# CLOCK.net
KiCad netlist of a schematic drawn in Altium Designer
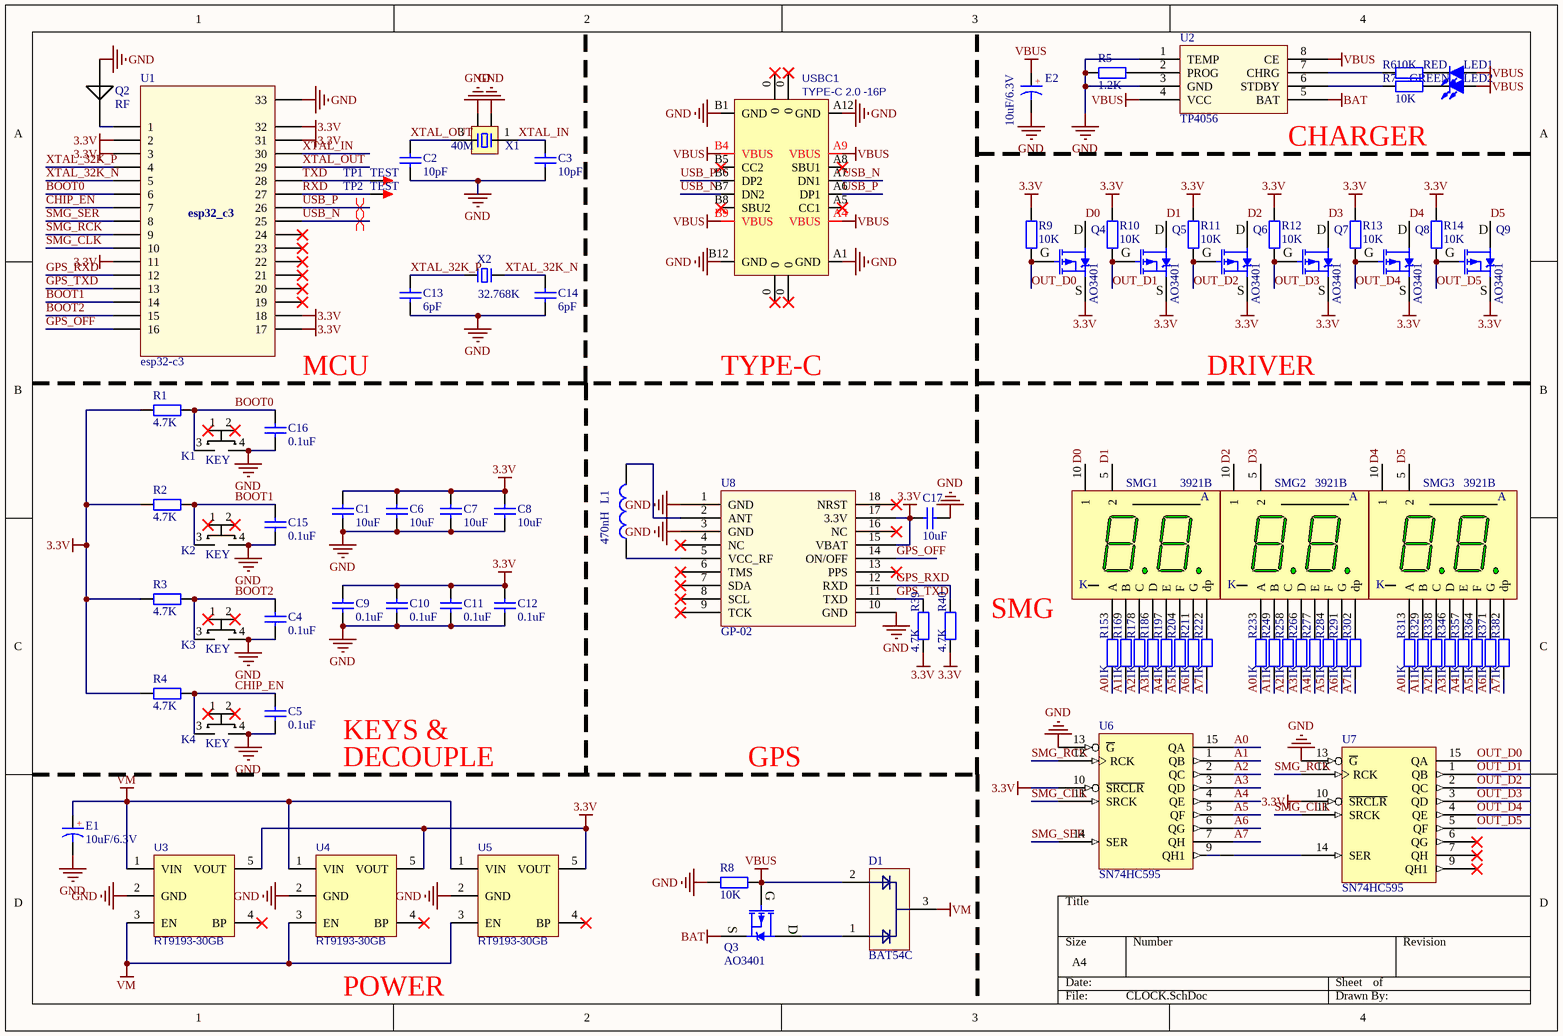
[diagram p0: CLOCK.SchDoc]

(export (version "E")
  (design (tool "Eeschema 10.0.6"))
  (components
    (comp (ref "C1")
      (value "10uF")
      (footprint "C0603_L")
      (description "贴片电容/MLCC电容")
      (libsource (lib "0.1 - 电阻-电容-电感-晶振-晶体-磁珠-电位器-法拉电容-馈通电容") (part "C"))
    )
    (comp (ref "C2")
      (value "10pF")
      (footprint "C0603_L")
      (description "贴片电容/MLCC电容")
      (libsource (lib "0.1 - 电阻-电容-电感-晶振-晶体-磁珠-电位器-法拉电容-馈通电容") (part "C"))
    )
    (comp (ref "C3")
      (value "10pF")
      (footprint "C0603_L")
      (description "贴片电容/MLCC电容")
      (libsource (lib "0.1 - 电阻-电容-电感-晶振-晶体-磁珠-电位器-法拉电容-馈通电容") (part "C"))
    )
    (comp (ref "C4")
      (value "0.1uF")
      (footprint "C0603_L")
      (description "贴片电容/MLCC电容")
      (libsource (lib "0.1 - 电阻-电容-电感-晶振-晶体-磁珠-电位器-法拉电容-馈通电容") (part "C"))
    )
    (comp (ref "C5")
      (value "0.1uF")
      (footprint "C0603_L")
      (description "贴片电容/MLCC电容")
      (libsource (lib "0.1 - 电阻-电容-电感-晶振-晶体-磁珠-电位器-法拉电容-馈通电容") (part "C"))
    )
    (comp (ref "C6")
      (value "10uF")
      (footprint "C0603_L")
      (description "贴片电容/MLCC电容")
      (libsource (lib "0.1 - 电阻-电容-电感-晶振-晶体-磁珠-电位器-法拉电容-馈通电容") (part "C"))
    )
    (comp (ref "C7")
      (value "10uF")
      (footprint "C0603_L")
      (description "贴片电容/MLCC电容")
      (libsource (lib "0.1 - 电阻-电容-电感-晶振-晶体-磁珠-电位器-法拉电容-馈通电容") (part "C"))
    )
    (comp (ref "C8")
      (value "10uF")
      (footprint "C0603_L")
      (description "贴片电容/MLCC电容")
      (libsource (lib "0.1 - 电阻-电容-电感-晶振-晶体-磁珠-电位器-法拉电容-馈通电容") (part "C"))
    )
    (comp (ref "C9")
      (value "0.1uF")
      (footprint "C0603_L")
      (description "贴片电容/MLCC电容")
      (libsource (lib "0.1 - 电阻-电容-电感-晶振-晶体-磁珠-电位器-法拉电容-馈通电容") (part "C"))
    )
    (comp (ref "C10")
      (value "0.1uF")
      (footprint "C0603_L")
      (description "贴片电容/MLCC电容")
      (libsource (lib "0.1 - 电阻-电容-电感-晶振-晶体-磁珠-电位器-法拉电容-馈通电容") (part "C"))
    )
    (comp (ref "C11")
      (value "0.1uF")
      (footprint "C0603_L")
      (description "贴片电容/MLCC电容")
      (libsource (lib "0.1 - 电阻-电容-电感-晶振-晶体-磁珠-电位器-法拉电容-馈通电容") (part "C"))
    )
    (comp (ref "C12")
      (value "0.1uF")
      (footprint "C0603_L")
      (description "贴片电容/MLCC电容")
      (libsource (lib "0.1 - 电阻-电容-电感-晶振-晶体-磁珠-电位器-法拉电容-馈通电容") (part "C"))
    )
    (comp (ref "C13")
      (value "6pF")
      (footprint "C0603_L")
      (description "贴片电容/MLCC电容")
      (libsource (lib "0.1 - 电阻-电容-电感-晶振-晶体-磁珠-电位器-法拉电容-馈通电容") (part "C"))
    )
    (comp (ref "C14")
      (value "6pF")
      (footprint "C0603_L")
      (description "贴片电容/MLCC电容")
      (libsource (lib "0.1 - 电阻-电容-电感-晶振-晶体-磁珠-电位器-法拉电容-馈通电容") (part "C"))
    )
    (comp (ref "C15")
      (value "0.1uF")
      (footprint "C0603_L")
      (description "贴片电容/MLCC电容")
      (libsource (lib "0.1 - 电阻-电容-电感-晶振-晶体-磁珠-电位器-法拉电容-馈通电容") (part "C"))
    )
    (comp (ref "C16")
      (value "0.1uF")
      (footprint "C0603_L")
      (description "贴片电容/MLCC电容")
      (libsource (lib "0.1 - 电阻-电容-电感-晶振-晶体-磁珠-电位器-法拉电容-馈通电容") (part "C"))
    )
    (comp (ref "C17")
      (value "10uF")
      (footprint "C0603_L")
      (description "贴片电容/MLCC电容")
      (libsource (lib "0.1 - 电阻-电容-电感-晶振-晶体-磁珠-电位器-法拉电容-馈通电容") (part "C"))
    )
    (comp (ref "D1")
      (value "BAT54C")
      (footprint "SOT23-3N")
      (description "两路肖特基二极管")
      (libsource (lib "0.2 - 二极管-TVS-ESD-整流桥-放电管") (part "BAT54C"))
    )
    (comp (ref "E1")
      (value "10uF/6.3V")
      (footprint "C_2012")
      (description "贴片钽电容")
      (libsource (lib "0.1 - 电阻-电容-电感-晶振-晶体-磁珠-电位器-法拉电容-馈通电容") (part "CT"))
    )
    (comp (ref "E2")
      (value "10uF/6.3V")
      (footprint "C_2012")
      (description "贴片钽电容")
      (libsource (lib "0.1 - 电阻-电容-电感-晶振-晶体-磁珠-电位器-法拉电容-馈通电容") (part "CT"))
    )
    (comp (ref "K1") (value "KEY") (footprint "KEY") (libsource (lib "CLOCK") (part "KEY")))
    (comp (ref "K2") (value "KEY") (footprint "KEY") (libsource (lib "CLOCK") (part "KEY")))
    (comp (ref "K3") (value "KEY") (footprint "KEY") (libsource (lib "CLOCK") (part "KEY")))
    (comp (ref "K4") (value "KEY") (footprint "KEY") (libsource (lib "CLOCK") (part "KEY")))
    (comp (ref "L1")
      (value "470nH")
      (footprint "L0603")
      (description "贴片小功率电感")
      (libsource (lib "0.1 - 电阻-电容-电感-晶振-晶体-磁珠-电位器-法拉电容-馈通电容") (part "L"))
    )
    (comp (ref "LED1")
      (value "RED")
      (footprint "LED0805_G")
      (description "贴片LED")
      (libsource (lib "0.3 - LED发光二极管-IR二极管_接收管-光耦") (part "LED-SMD"))
    )
    (comp (ref "LED2")
      (value "GREEN")
      (footprint "LED0805_G")
      (description "贴片LED")
      (libsource (lib "0.3 - LED发光二极管-IR二极管_接收管-光耦") (part "LED-SMD"))
    )
    (comp (ref "Q2") (value "RF") (footprint "RF") (libsource (lib "motor") (part "RF")))
    (comp (ref "Q3")
      (value "AO3401")
      (footprint "SOT23-3N")
      (description "P沟道 30V/4.2A")
      (libsource (lib "0.4 - 三极管-场效应管-可控硅") (part "AO3401"))
    )
    (comp (ref "Q4")
      (value "AO3401")
      (footprint "SOT23-3N")
      (description "P沟道 30V/4.2A")
      (libsource (lib "0.4 - 三极管-场效应管-可控硅") (part "AO3401"))
    )
    (comp (ref "Q5")
      (value "AO3401")
      (footprint "SOT23-3N")
      (description "P沟道 30V/4.2A")
      (libsource (lib "0.4 - 三极管-场效应管-可控硅") (part "AO3401"))
    )
    (comp (ref "Q6")
      (value "AO3401")
      (footprint "SOT23-3N")
      (description "P沟道 30V/4.2A")
      (libsource (lib "0.4 - 三极管-场效应管-可控硅") (part "AO3401"))
    )
    (comp (ref "Q7")
      (value "AO3401")
      (footprint "SOT23-3N")
      (description "P沟道 30V/4.2A")
      (libsource (lib "0.4 - 三极管-场效应管-可控硅") (part "AO3401"))
    )
    (comp (ref "Q8")
      (value "AO3401")
      (footprint "SOT23-3N")
      (description "P沟道 30V/4.2A")
      (libsource (lib "0.4 - 三极管-场效应管-可控硅") (part "AO3401"))
    )
    (comp (ref "Q9")
      (value "AO3401")
      (footprint "SOT23-3N")
      (description "P沟道 30V/4.2A")
      (libsource (lib "0.4 - 三极管-场效应管-可控硅") (part "AO3401"))
    )
    (comp (ref "R1")
      (value "4.7K")
      (footprint "R0603_L")
      (description "贴片电阻")
      (libsource (lib "0.1 - 电阻-电容-电感-晶振-晶体-磁珠-电位器-法拉电容-馈通电容") (part "R"))
    )
    (comp (ref "R2")
      (value "4.7K")
      (footprint "R0603_L")
      (description "贴片电阻")
      (libsource (lib "0.1 - 电阻-电容-电感-晶振-晶体-磁珠-电位器-法拉电容-馈通电容") (part "R"))
    )
    (comp (ref "R3")
      (value "4.7K")
      (footprint "R0603_L")
      (description "贴片电阻")
      (libsource (lib "0.1 - 电阻-电容-电感-晶振-晶体-磁珠-电位器-法拉电容-馈通电容") (part "R"))
    )
    (comp (ref "R4")
      (value "4.7K")
      (footprint "R0603_L")
      (description "贴片电阻")
      (libsource (lib "0.1 - 电阻-电容-电感-晶振-晶体-磁珠-电位器-法拉电容-馈通电容") (part "R"))
    )
    (comp (ref "R5")
      (value "1.2K")
      (footprint "R0603_L")
      (description "贴片电阻")
      (libsource (lib "0.1 - 电阻-电容-电感-晶振-晶体-磁珠-电位器-法拉电容-馈通电容") (part "R"))
    )
    (comp (ref "R6")
      (value "10K")
      (footprint "R0603_L")
      (description "贴片电阻")
      (libsource (lib "0.1 - 电阻-电容-电感-晶振-晶体-磁珠-电位器-法拉电容-馈通电容") (part "R"))
    )
    (comp (ref "R7")
      (value "10K")
      (footprint "R0603_L")
      (description "贴片电阻")
      (libsource (lib "0.1 - 电阻-电容-电感-晶振-晶体-磁珠-电位器-法拉电容-馈通电容") (part "R"))
    )
    (comp (ref "R8")
      (value "10K")
      (footprint "R0603_L")
      (description "贴片电阻")
      (libsource (lib "0.1 - 电阻-电容-电感-晶振-晶体-磁珠-电位器-法拉电容-馈通电容") (part "R"))
    )
    (comp (ref "R9")
      (value "10K")
      (footprint "R0603_L")
      (description "贴片电阻")
      (libsource (lib "0.1 - 电阻-电容-电感-晶振-晶体-磁珠-电位器-法拉电容-馈通电容") (part "R"))
    )
    (comp (ref "R10")
      (value "10K")
      (footprint "R0603_L")
      (description "贴片电阻")
      (libsource (lib "0.1 - 电阻-电容-电感-晶振-晶体-磁珠-电位器-法拉电容-馈通电容") (part "R"))
    )
    (comp (ref "R11")
      (value "10K")
      (footprint "R0603_L")
      (description "贴片电阻")
      (libsource (lib "0.1 - 电阻-电容-电感-晶振-晶体-磁珠-电位器-法拉电容-馈通电容") (part "R"))
    )
    (comp (ref "R12")
      (value "10K")
      (footprint "R0603_L")
      (description "贴片电阻")
      (libsource (lib "0.1 - 电阻-电容-电感-晶振-晶体-磁珠-电位器-法拉电容-馈通电容") (part "R"))
    )
    (comp (ref "R13")
      (value "10K")
      (footprint "R0603_L")
      (description "贴片电阻")
      (libsource (lib "0.1 - 电阻-电容-电感-晶振-晶体-磁珠-电位器-法拉电容-馈通电容") (part "R"))
    )
    (comp (ref "R14")
      (value "10K")
      (footprint "R0603_L")
      (description "贴片电阻")
      (libsource (lib "0.1 - 电阻-电容-电感-晶振-晶体-磁珠-电位器-法拉电容-馈通电容") (part "R"))
    )
    (comp (ref "R15")
      (value "1K")
      (footprint "R0603_L")
      (description "贴片电阻")
      (libsource (lib "0.1 - 电阻-电容-电感-晶振-晶体-磁珠-电位器-法拉电容-馈通电容") (part "R"))
    )
    (comp (ref "R16")
      (value "1K")
      (footprint "R0603_L")
      (description "贴片电阻")
      (libsource (lib "0.1 - 电阻-电容-电感-晶振-晶体-磁珠-电位器-法拉电容-馈通电容") (part "R"))
    )
    (comp (ref "R17")
      (value "1K")
      (footprint "R0603_L")
      (description "贴片电阻")
      (libsource (lib "0.1 - 电阻-电容-电感-晶振-晶体-磁珠-电位器-法拉电容-馈通电容") (part "R"))
    )
    (comp (ref "R18")
      (value "1K")
      (footprint "R0603_L")
      (description "贴片电阻")
      (libsource (lib "0.1 - 电阻-电容-电感-晶振-晶体-磁珠-电位器-法拉电容-馈通电容") (part "R"))
    )
    (comp (ref "R19")
      (value "1K")
      (footprint "R0603_L")
      (description "贴片电阻")
      (libsource (lib "0.1 - 电阻-电容-电感-晶振-晶体-磁珠-电位器-法拉电容-馈通电容") (part "R"))
    )
    (comp (ref "R20")
      (value "1K")
      (footprint "R0603_L")
      (description "贴片电阻")
      (libsource (lib "0.1 - 电阻-电容-电感-晶振-晶体-磁珠-电位器-法拉电容-馈通电容") (part "R"))
    )
    (comp (ref "R21")
      (value "1K")
      (footprint "R0603_L")
      (description "贴片电阻")
      (libsource (lib "0.1 - 电阻-电容-电感-晶振-晶体-磁珠-电位器-法拉电容-馈通电容") (part "R"))
    )
    (comp (ref "R22")
      (value "1K")
      (footprint "R0603_L")
      (description "贴片电阻")
      (libsource (lib "0.1 - 电阻-电容-电感-晶振-晶体-磁珠-电位器-法拉电容-馈通电容") (part "R"))
    )
    (comp (ref "R23")
      (value "1K")
      (footprint "R0603_L")
      (description "贴片电阻")
      (libsource (lib "0.1 - 电阻-电容-电感-晶振-晶体-磁珠-电位器-法拉电容-馈通电容") (part "R"))
    )
    (comp (ref "R24")
      (value "1K")
      (footprint "R0603_L")
      (description "贴片电阻")
      (libsource (lib "0.1 - 电阻-电容-电感-晶振-晶体-磁珠-电位器-法拉电容-馈通电容") (part "R"))
    )
    (comp (ref "R25")
      (value "1K")
      (footprint "R0603_L")
      (description "贴片电阻")
      (libsource (lib "0.1 - 电阻-电容-电感-晶振-晶体-磁珠-电位器-法拉电容-馈通电容") (part "R"))
    )
    (comp (ref "R26")
      (value "1K")
      (footprint "R0603_L")
      (description "贴片电阻")
      (libsource (lib "0.1 - 电阻-电容-电感-晶振-晶体-磁珠-电位器-法拉电容-馈通电容") (part "R"))
    )
    (comp (ref "R27")
      (value "1K")
      (footprint "R0603_L")
      (description "贴片电阻")
      (libsource (lib "0.1 - 电阻-电容-电感-晶振-晶体-磁珠-电位器-法拉电容-馈通电容") (part "R"))
    )
    (comp (ref "R28")
      (value "1K")
      (footprint "R0603_L")
      (description "贴片电阻")
      (libsource (lib "0.1 - 电阻-电容-电感-晶振-晶体-磁珠-电位器-法拉电容-馈通电容") (part "R"))
    )
    (comp (ref "R29")
      (value "1K")
      (footprint "R0603_L")
      (description "贴片电阻")
      (libsource (lib "0.1 - 电阻-电容-电感-晶振-晶体-磁珠-电位器-法拉电容-馈通电容") (part "R"))
    )
    (comp (ref "R30")
      (value "1K")
      (footprint "R0603_L")
      (description "贴片电阻")
      (libsource (lib "0.1 - 电阻-电容-电感-晶振-晶体-磁珠-电位器-法拉电容-馈通电容") (part "R"))
    )
    (comp (ref "R31")
      (value "1K")
      (footprint "R0603_L")
      (description "贴片电阻")
      (libsource (lib "0.1 - 电阻-电容-电感-晶振-晶体-磁珠-电位器-法拉电容-馈通电容") (part "R"))
    )
    (comp (ref "R32")
      (value "1K")
      (footprint "R0603_L")
      (description "贴片电阻")
      (libsource (lib "0.1 - 电阻-电容-电感-晶振-晶体-磁珠-电位器-法拉电容-馈通电容") (part "R"))
    )
    (comp (ref "R33")
      (value "1K")
      (footprint "R0603_L")
      (description "贴片电阻")
      (libsource (lib "0.1 - 电阻-电容-电感-晶振-晶体-磁珠-电位器-法拉电容-馈通电容") (part "R"))
    )
    (comp (ref "R34")
      (value "1K")
      (footprint "R0603_L")
      (description "贴片电阻")
      (libsource (lib "0.1 - 电阻-电容-电感-晶振-晶体-磁珠-电位器-法拉电容-馈通电容") (part "R"))
    )
    (comp (ref "R35")
      (value "1K")
      (footprint "R0603_L")
      (description "贴片电阻")
      (libsource (lib "0.1 - 电阻-电容-电感-晶振-晶体-磁珠-电位器-法拉电容-馈通电容") (part "R"))
    )
    (comp (ref "R36")
      (value "1K")
      (footprint "R0603_L")
      (description "贴片电阻")
      (libsource (lib "0.1 - 电阻-电容-电感-晶振-晶体-磁珠-电位器-法拉电容-馈通电容") (part "R"))
    )
    (comp (ref "R37")
      (value "1K")
      (footprint "R0603_L")
      (description "贴片电阻")
      (libsource (lib "0.1 - 电阻-电容-电感-晶振-晶体-磁珠-电位器-法拉电容-馈通电容") (part "R"))
    )
    (comp (ref "R38")
      (value "1K")
      (footprint "R0603_L")
      (description "贴片电阻")
      (libsource (lib "0.1 - 电阻-电容-电感-晶振-晶体-磁珠-电位器-法拉电容-馈通电容") (part "R"))
    )
    (comp (ref "R39")
      (value "4.7K")
      (footprint "R0603_L")
      (description "贴片电阻")
      (libsource (lib "0.1 - 电阻-电容-电感-晶振-晶体-磁珠-电位器-法拉电容-馈通电容") (part "R"))
    )
    (comp (ref "R40")
      (value "4.7K")
      (footprint "R0603_L")
      (description "贴片电阻")
      (libsource (lib "0.1 - 电阻-电容-电感-晶振-晶体-磁珠-电位器-法拉电容-馈通电容") (part "R"))
    )
    (comp (ref "SMG1")
      (value "3921B")
      (footprint "GS3922CPG-G")
      (description "0.39寸2位共阳数码管")
      (libsource (lib "1.3 - 数码管-TFT-OLED屏") (part "3921B"))
    )
    (comp (ref "SMG2")
      (value "3921B")
      (footprint "GS3922CPG-G")
      (description "0.39寸2位共阳数码管")
      (libsource (lib "1.3 - 数码管-TFT-OLED屏") (part "3921B"))
    )
    (comp (ref "SMG3")
      (value "3921B")
      (footprint "GS3922CPG-G")
      (description "0.39寸2位共阳数码管")
      (libsource (lib "1.3 - 数码管-TFT-OLED屏") (part "3921B"))
    )
    (comp (ref "TP1")
      (value "TEST")
      (footprint "TEST 1.6")
      (description "测试点")
      (libsource (lib "0.5 - 按键_开关_蜂鸣器_保险丝_电池_测试点_Mark点_铜柱") (part "TEST"))
    )
    (comp (ref "TP2")
      (value "TEST")
      (footprint "TEST 1.6")
      (description "测试点")
      (libsource (lib "0.5 - 按键_开关_蜂鸣器_保险丝_电池_测试点_Mark点_铜柱") (part "TEST"))
    )
    (comp (ref "U1") (value "esp32-c3") (footprint "QFN32 5x5_M") (libsource (lib "motor") (part "esp32-c3")))
    (comp (ref "U2") (value "TP4056") (footprint "SOP-8") (libsource (lib "CLOCK") (part "TP4056")))
    (comp (ref "U3")
      (value "RT9193-30GB")
      (footprint "SOT-23-5")
      (description "LDO 3.0V/0.3A")
      (libsource (lib "0.7 - 电源类芯片") (part "RT9193-30GB"))
    )
    (comp (ref "U4")
      (value "RT9193-30GB")
      (footprint "SOT-23-5")
      (description "LDO 3.0V/0.3A")
      (libsource (lib "0.7 - 电源类芯片") (part "RT9193-30GB"))
    )
    (comp (ref "U5")
      (value "RT9193-30GB")
      (footprint "SOT-23-5")
      (description "LDO 3.0V/0.3A")
      (libsource (lib "0.7 - 电源类芯片") (part "RT9193-30GB"))
    )
    (comp (ref "U6")
      (value "SN74HC595")
      (footprint "SO16")
      (description "8-BIT SFT REG WIRTH OUTPUT LCH")
      (libsource (lib "1.1 - 74系列TTL逻辑芯片") (part "SN74HC595"))
    )
    (comp (ref "U7")
      (value "SN74HC595")
      (footprint "SO16")
      (description "8-BIT SFT REG WIRTH OUTPUT LCH")
      (libsource (lib "1.1 - 74系列TTL逻辑芯片") (part "SN74HC595"))
    )
    (comp (ref "U8") (value "GP-02") (footprint "GP-02") (libsource (lib "CLOCK") (part "GP-02")))
    (comp (ref "USBC1")
      (value "TYPE-C 2.0 -16P")
      (footprint "USB-C-SMD_16P")
      (description "USB2.0_Type-C_16Pin母座")
      (libsource (lib "0.6 - 电源_RJ45以太网_音频_SD-TF_SIM_ USB Type-C_HDMI插座") (part "USB2.0_Type-C_16Pin"))
    )
    (comp (ref "X1")
      (value "40M")
      (footprint "XTAL-3225-4P")
      (description "4脚无源晶振(谐振器）")
      (libsource (lib "0.1 - 电阻-电容-电感-晶振-晶体-磁珠-电位器-法拉电容-馈通电容") (part "XTAL-4P"))
    )
    (comp (ref "X2")
      (value "32.768K")
      (footprint "XTAL-3x8-WS")
      (description "2脚无源晶振(谐振器）")
      (libsource (lib "0.1 - 电阻-电容-电感-晶振-晶体-磁珠-电位器-法拉电容-馈通电容") (part "XTAL-2P"))
    )
  )
  (nets
    (net (code "1") (name "/A0") (class "Default")
      (node (ref "R15") (pin "1") (pinfunction "1_1") (pintype "passive"))
      (node (ref "R23") (pin "1") (pinfunction "1_1") (pintype "passive"))
      (node (ref "R31") (pin "1") (pinfunction "1_1") (pintype "passive"))
      (node (ref "U6") (pin "15") (pinfunction "QA_15") (pintype "tri_state"))
    )
    (net (code "2") (name "/A1") (class "Default")
      (node (ref "R16") (pin "1") (pinfunction "1_1") (pintype "passive"))
      (node (ref "R24") (pin "1") (pinfunction "1_1") (pintype "passive"))
      (node (ref "R32") (pin "1") (pinfunction "1_1") (pintype "passive"))
      (node (ref "U6") (pin "1") (pinfunction "QB_1") (pintype "output"))
    )
    (net (code "3") (name "/A2") (class "Default")
      (node (ref "R17") (pin "1") (pinfunction "1_1") (pintype "passive"))
      (node (ref "R25") (pin "1") (pinfunction "1_1") (pintype "passive"))
      (node (ref "R33") (pin "1") (pinfunction "1_1") (pintype "passive"))
      (node (ref "U6") (pin "2") (pinfunction "QC_2") (pintype "output"))
    )
    (net (code "4") (name "/A3") (class "Default")
      (node (ref "R18") (pin "1") (pinfunction "1_1") (pintype "passive"))
      (node (ref "R26") (pin "1") (pinfunction "1_1") (pintype "passive"))
      (node (ref "R34") (pin "1") (pinfunction "1_1") (pintype "passive"))
      (node (ref "U6") (pin "3") (pinfunction "QD_3") (pintype "output"))
    )
    (net (code "5") (name "/A4") (class "Default")
      (node (ref "R19") (pin "1") (pinfunction "1_1") (pintype "passive"))
      (node (ref "R27") (pin "1") (pinfunction "1_1") (pintype "passive"))
      (node (ref "R35") (pin "1") (pinfunction "1_1") (pintype "passive"))
      (node (ref "U6") (pin "4") (pinfunction "QE_4") (pintype "output"))
    )
    (net (code "6") (name "/A5") (class "Default")
      (node (ref "R20") (pin "1") (pinfunction "1_1") (pintype "passive"))
      (node (ref "R28") (pin "1") (pinfunction "1_1") (pintype "passive"))
      (node (ref "R36") (pin "1") (pinfunction "1_1") (pintype "passive"))
      (node (ref "U6") (pin "5") (pinfunction "QF_5") (pintype "output"))
    )
    (net (code "7") (name "/A6") (class "Default")
      (node (ref "R21") (pin "1") (pinfunction "1_1") (pintype "passive"))
      (node (ref "R29") (pin "1") (pinfunction "1_1") (pintype "passive"))
      (node (ref "R37") (pin "1") (pinfunction "1_1") (pintype "passive"))
      (node (ref "U6") (pin "6") (pinfunction "QG_6") (pintype "output"))
    )
    (net (code "8") (name "/A7") (class "Default")
      (node (ref "R22") (pin "1") (pinfunction "1_1") (pintype "passive"))
      (node (ref "R30") (pin "1") (pinfunction "1_1") (pintype "passive"))
      (node (ref "R38") (pin "1") (pinfunction "1_1") (pintype "passive"))
      (node (ref "U6") (pin "7") (pinfunction "QH_7") (pintype "tri_state"))
    )
    (net (code "9") (name "/BOOT0") (class "Default")
      (node (ref "C16") (pin "2") (pinfunction "2_2") (pintype "passive"))
      (node (ref "K1") (pin "3") (pintype "passive"))
      (node (ref "R1") (pin "2") (pinfunction "2_2") (pintype "passive"))
      (node (ref "U1") (pin "6") (pinfunction "6_6") (pintype "passive"))
    )
    (net (code "10") (name "/BOOT1") (class "Default")
      (node (ref "C15") (pin "2") (pinfunction "2_2") (pintype "passive"))
      (node (ref "K2") (pin "3") (pintype "passive"))
      (node (ref "R2") (pin "2") (pinfunction "2_2") (pintype "passive"))
      (node (ref "U1") (pin "14") (pinfunction "14_14") (pintype "passive"))
    )
    (net (code "11") (name "/BOOT2") (class "Default")
      (node (ref "C4") (pin "2") (pinfunction "2_2") (pintype "passive"))
      (node (ref "K3") (pin "3") (pintype "passive"))
      (node (ref "R3") (pin "2") (pinfunction "2_2") (pintype "passive"))
      (node (ref "U1") (pin "15") (pinfunction "15_15") (pintype "passive"))
    )
    (net (code "12") (name "/CHIP_EN") (class "Default")
      (node (ref "C5") (pin "2") (pinfunction "2_2") (pintype "passive"))
      (node (ref "K4") (pin "3") (pintype "passive"))
      (node (ref "R4") (pin "2") (pinfunction "2_2") (pintype "passive"))
      (node (ref "U1") (pin "7") (pinfunction "7_7") (pintype "passive"))
    )
    (net (code "13") (name "/D0") (class "Default")
      (node (ref "Q4") (pin "3") (pinfunction "D_3") (pintype "passive"))
      (node (ref "SMG1") (pin "10") (pinfunction "1_10") (pintype "passive"))
    )
    (net (code "14") (name "/D1") (class "Default")
      (node (ref "Q5") (pin "3") (pinfunction "D_3") (pintype "passive"))
      (node (ref "SMG1") (pin "5") (pinfunction "2_5") (pintype "passive"))
    )
    (net (code "15") (name "/D2") (class "Default")
      (node (ref "Q6") (pin "3") (pinfunction "D_3") (pintype "passive"))
      (node (ref "SMG2") (pin "10") (pinfunction "1_10") (pintype "passive"))
    )
    (net (code "16") (name "/D3") (class "Default")
      (node (ref "Q7") (pin "3") (pinfunction "D_3") (pintype "passive"))
      (node (ref "SMG2") (pin "5") (pinfunction "2_5") (pintype "passive"))
    )
    (net (code "17") (name "/D4") (class "Default")
      (node (ref "Q8") (pin "3") (pinfunction "D_3") (pintype "passive"))
      (node (ref "SMG3") (pin "10") (pinfunction "1_10") (pintype "passive"))
    )
    (net (code "18") (name "/D5") (class "Default")
      (node (ref "Q9") (pin "3") (pinfunction "D_3") (pintype "passive"))
      (node (ref "SMG3") (pin "5") (pinfunction "2_5") (pintype "passive"))
    )
    (net (code "19") (name "/GPS_OFF") (class "Default")
      (node (ref "U1") (pin "16") (pinfunction "16_16") (pintype "passive"))
      (node (ref "U8") (pin "14") (pinfunction "ON/OFF_14") (pintype "passive"))
    )
    (net (code "20") (name "/GPS_RXD") (class "Default")
      (node (ref "R40") (pin "2") (pinfunction "2_2") (pintype "passive"))
      (node (ref "U1") (pin "12") (pinfunction "12_12") (pintype "passive"))
      (node (ref "U8") (pin "12") (pinfunction "RXD_12") (pintype "passive"))
    )
    (net (code "21") (name "/GPS_TXD") (class "Default")
      (node (ref "R39") (pin "2") (pinfunction "2_2") (pintype "passive"))
      (node (ref "U1") (pin "13") (pinfunction "13_13") (pintype "passive"))
      (node (ref "U8") (pin "11") (pinfunction "TXD_11") (pintype "passive"))
    )
    (net (code "22") (name "/OUT_D0") (class "Default")
      (node (ref "Q4") (pin "1") (pinfunction "G_1") (pintype "passive"))
      (node (ref "R9") (pin "1") (pinfunction "1_1") (pintype "passive"))
      (node (ref "U7") (pin "15") (pinfunction "QA_15") (pintype "tri_state"))
    )
    (net (code "23") (name "/OUT_D1") (class "Default")
      (node (ref "Q5") (pin "1") (pinfunction "G_1") (pintype "passive"))
      (node (ref "R10") (pin "1") (pinfunction "1_1") (pintype "passive"))
      (node (ref "U7") (pin "1") (pinfunction "QB_1") (pintype "output"))
    )
    (net (code "24") (name "/OUT_D2") (class "Default")
      (node (ref "Q6") (pin "1") (pinfunction "G_1") (pintype "passive"))
      (node (ref "R11") (pin "1") (pinfunction "1_1") (pintype "passive"))
      (node (ref "U7") (pin "2") (pinfunction "QC_2") (pintype "output"))
    )
    (net (code "25") (name "/OUT_D3") (class "Default")
      (node (ref "Q7") (pin "1") (pinfunction "G_1") (pintype "passive"))
      (node (ref "R12") (pin "1") (pinfunction "1_1") (pintype "passive"))
      (node (ref "U7") (pin "3") (pinfunction "QD_3") (pintype "output"))
    )
    (net (code "26") (name "/OUT_D4") (class "Default")
      (node (ref "Q8") (pin "1") (pinfunction "G_1") (pintype "passive"))
      (node (ref "R13") (pin "1") (pinfunction "1_1") (pintype "passive"))
      (node (ref "U7") (pin "4") (pinfunction "QE_4") (pintype "output"))
    )
    (net (code "27") (name "/OUT_D5") (class "Default")
      (node (ref "Q9") (pin "1") (pinfunction "G_1") (pintype "passive"))
      (node (ref "R14") (pin "1") (pinfunction "1_1") (pintype "passive"))
      (node (ref "U7") (pin "5") (pinfunction "QF_5") (pintype "output"))
    )
    (net (code "28") (name "/RXD") (class "Default")
      (node (ref "TP2") (pin "1") (pinfunction "1_1") (pintype "passive"))
      (node (ref "U1") (pin "27") (pinfunction "27_27") (pintype "passive"))
    )
    (net (code "29") (name "/SMG_CLK") (class "Default")
      (node (ref "U1") (pin "10") (pinfunction "10_10") (pintype "passive"))
      (node (ref "U6") (pin "11") (pinfunction "SRCK_11") (pintype "input"))
      (node (ref "U7") (pin "11") (pinfunction "SRCK_11") (pintype "input"))
    )
    (net (code "30") (name "/SMG_RCK") (class "Default")
      (node (ref "U1") (pin "9") (pinfunction "9_9") (pintype "passive"))
      (node (ref "U6") (pin "12") (pinfunction "RCK_12") (pintype "input"))
      (node (ref "U7") (pin "12") (pinfunction "RCK_12") (pintype "input"))
    )
    (net (code "31") (name "/SMG_SER") (class "Default")
      (node (ref "U1") (pin "8") (pinfunction "8_8") (pintype "passive"))
      (node (ref "U6") (pin "14") (pinfunction "SER_14") (pintype "input"))
    )
    (net (code "32") (name "/TXD") (class "Default")
      (node (ref "TP1") (pin "1") (pinfunction "1_1") (pintype "passive"))
      (node (ref "U1") (pin "28") (pinfunction "28_28") (pintype "passive"))
    )
    (net (code "33") (name "/USB_N") (class "Default")
      (node (ref "U1") (pin "25") (pinfunction "25_25") (pintype "passive"))
      (node (ref "USBC1") (pin "A7") (pinfunction "DN1_A7") (pintype "passive"))
      (node (ref "USBC1") (pin "B7") (pinfunction "DN2_B7") (pintype "passive"))
    )
    (net (code "34") (name "/USB_P") (class "Default")
      (node (ref "U1") (pin "26") (pinfunction "26_26") (pintype "passive"))
      (node (ref "USBC1") (pin "A6") (pinfunction "DP1_A6") (pintype "passive"))
      (node (ref "USBC1") (pin "B6") (pinfunction "DP2_B6") (pintype "passive"))
    )
    (net (code "35") (name "/XTAL_32K_N") (class "Default")
      (node (ref "C14") (pin "2") (pinfunction "2_2") (pintype "passive"))
      (node (ref "U1") (pin "5") (pinfunction "5_5") (pintype "passive"))
      (node (ref "X2") (pin "2") (pinfunction "2_2") (pintype "passive"))
    )
    (net (code "36") (name "/XTAL_32K_P") (class "Default")
      (node (ref "C13") (pin "2") (pinfunction "2_2") (pintype "passive"))
      (node (ref "U1") (pin "4") (pinfunction "4_4") (pintype "passive"))
      (node (ref "X2") (pin "1") (pinfunction "1_1") (pintype "passive"))
    )
    (net (code "37") (name "/XTAL_IN") (class "Default")
      (node (ref "C3") (pin "2") (pinfunction "2_2") (pintype "passive"))
      (node (ref "U1") (pin "30") (pinfunction "30_30") (pintype "passive"))
      (node (ref "X1") (pin "1") (pinfunction "1_1") (pintype "passive"))
    )
    (net (code "38") (name "/XTAL_OUT") (class "Default")
      (node (ref "C2") (pin "2") (pinfunction "2_2") (pintype "passive"))
      (node (ref "U1") (pin "29") (pinfunction "29_29") (pintype "passive"))
      (node (ref "X1") (pin "3") (pinfunction "3_3") (pintype "passive"))
    )
    (net (code "39") (name "3.3V") (class "Default")
      (node (ref "C1") (pin "2") (pinfunction "2_2") (pintype "passive"))
      (node (ref "C10") (pin "2") (pinfunction "2_2") (pintype "passive"))
      (node (ref "C11") (pin "2") (pinfunction "2_2") (pintype "passive"))
      (node (ref "C12") (pin "2") (pinfunction "2_2") (pintype "passive"))
      (node (ref "C17") (pin "2") (pinfunction "2_2") (pintype "passive"))
      (node (ref "C6") (pin "2") (pinfunction "2_2") (pintype "passive"))
      (node (ref "C7") (pin "2") (pinfunction "2_2") (pintype "passive"))
      (node (ref "C8") (pin "2") (pinfunction "2_2") (pintype "passive"))
      (node (ref "C9") (pin "2") (pinfunction "2_2") (pintype "passive"))
      (node (ref "Q4") (pin "2") (pinfunction "S_2") (pintype "passive"))
      (node (ref "Q5") (pin "2") (pinfunction "S_2") (pintype "passive"))
      (node (ref "Q6") (pin "2") (pinfunction "S_2") (pintype "passive"))
      (node (ref "Q7") (pin "2") (pinfunction "S_2") (pintype "passive"))
      (node (ref "Q8") (pin "2") (pinfunction "S_2") (pintype "passive"))
      (node (ref "Q9") (pin "2") (pinfunction "S_2") (pintype "passive"))
      (node (ref "R1") (pin "1") (pinfunction "1_1") (pintype "passive"))
      (node (ref "R10") (pin "2") (pinfunction "2_2") (pintype "passive"))
      (node (ref "R11") (pin "2") (pinfunction "2_2") (pintype "passive"))
      (node (ref "R12") (pin "2") (pinfunction "2_2") (pintype "passive"))
      (node (ref "R13") (pin "2") (pinfunction "2_2") (pintype "passive"))
      (node (ref "R14") (pin "2") (pinfunction "2_2") (pintype "passive"))
      (node (ref "R2") (pin "1") (pinfunction "1_1") (pintype "passive"))
      (node (ref "R3") (pin "1") (pinfunction "1_1") (pintype "passive"))
      (node (ref "R39") (pin "1") (pinfunction "1_1") (pintype "passive"))
      (node (ref "R4") (pin "1") (pinfunction "1_1") (pintype "passive"))
      (node (ref "R40") (pin "1") (pinfunction "1_1") (pintype "passive"))
      (node (ref "R9") (pin "2") (pinfunction "2_2") (pintype "passive"))
      (node (ref "U1") (pin "11") (pinfunction "11_11") (pintype "passive"))
      (node (ref "U1") (pin "17") (pinfunction "17_17") (pintype "passive"))
      (node (ref "U1") (pin "18") (pinfunction "18_18") (pintype "passive"))
      (node (ref "U1") (pin "2") (pinfunction "2_2") (pintype "passive"))
      (node (ref "U1") (pin "3") (pinfunction "3_3") (pintype "passive"))
      (node (ref "U1") (pin "31") (pinfunction "31_31") (pintype "passive"))
      (node (ref "U1") (pin "32") (pinfunction "32_32") (pintype "passive"))
      (node (ref "U3") (pin "5") (pinfunction "VOUT_5") (pintype "passive"))
      (node (ref "U4") (pin "5") (pinfunction "VOUT_5") (pintype "passive"))
      (node (ref "U5") (pin "5") (pinfunction "VOUT_5") (pintype "passive"))
      (node (ref "U6") (pin "10") (pinfunction "~{SRCLR}_10") (pintype "input"))
      (node (ref "U7") (pin "10") (pinfunction "~{SRCLR}_10") (pintype "input"))
      (node (ref "U8") (pin "15") (pinfunction "VBAT_15") (pintype "passive"))
      (node (ref "U8") (pin "17") (pinfunction "3.3V_17") (pintype "passive"))
    )
    (net (code "40") (name "BAT") (class "Default")
      (node (ref "Q3") (pin "2") (pinfunction "S_2") (pintype "passive"))
      (node (ref "U2") (pin "5") (pinfunction "BAT_5") (pintype "passive"))
    )
    (net (code "41") (name "GND") (class "Default")
      (node (ref "C1") (pin "1") (pinfunction "1_1") (pintype "passive"))
      (node (ref "C10") (pin "1") (pinfunction "1_1") (pintype "passive"))
      (node (ref "C11") (pin "1") (pinfunction "1_1") (pintype "passive"))
      (node (ref "C12") (pin "1") (pinfunction "1_1") (pintype "passive"))
      (node (ref "C13") (pin "1") (pinfunction "1_1") (pintype "passive"))
      (node (ref "C14") (pin "1") (pinfunction "1_1") (pintype "passive"))
      (node (ref "C15") (pin "1") (pinfunction "1_1") (pintype "passive"))
      (node (ref "C16") (pin "1") (pinfunction "1_1") (pintype "passive"))
      (node (ref "C17") (pin "1") (pinfunction "1_1") (pintype "passive"))
      (node (ref "C2") (pin "1") (pinfunction "1_1") (pintype "passive"))
      (node (ref "C3") (pin "1") (pinfunction "1_1") (pintype "passive"))
      (node (ref "C4") (pin "1") (pinfunction "1_1") (pintype "passive"))
      (node (ref "C5") (pin "1") (pinfunction "1_1") (pintype "passive"))
      (node (ref "C6") (pin "1") (pinfunction "1_1") (pintype "passive"))
      (node (ref "C7") (pin "1") (pinfunction "1_1") (pintype "passive"))
      (node (ref "C8") (pin "1") (pinfunction "1_1") (pintype "passive"))
      (node (ref "C9") (pin "1") (pinfunction "1_1") (pintype "passive"))
      (node (ref "E1") (pin "2") (pinfunction "K_2") (pintype "passive"))
      (node (ref "E2") (pin "2") (pinfunction "K_2") (pintype "passive"))
      (node (ref "K1") (pin "4") (pintype "passive"))
      (node (ref "K2") (pin "4") (pintype "passive"))
      (node (ref "K3") (pin "4") (pintype "passive"))
      (node (ref "K4") (pin "4") (pintype "passive"))
      (node (ref "Q2") (pin "1") (pinfunction "1_1") (pintype "passive"))
      (node (ref "R5") (pin "1") (pinfunction "1_1") (pintype "passive"))
      (node (ref "R8") (pin "1") (pinfunction "1_1") (pintype "passive"))
      (node (ref "U1") (pin "33") (pinfunction "33_33") (pintype "passive"))
      (node (ref "U2") (pin "1") (pinfunction "TEMP_1") (pintype "passive"))
      (node (ref "U2") (pin "3") (pinfunction "GND_3") (pintype "passive"))
      (node (ref "U3") (pin "2") (pinfunction "GND_2") (pintype "passive"))
      (node (ref "U4") (pin "2") (pinfunction "GND_2") (pintype "passive"))
      (node (ref "U5") (pin "2") (pinfunction "GND_2") (pintype "passive"))
      (node (ref "U6") (pin "13") (pinfunction "~{G}_13") (pintype "input"))
      (node (ref "U6") (pin "8") (pinfunction "GND_8") (pintype "power_in"))
      (node (ref "U7") (pin "13") (pinfunction "~{G}_13") (pintype "input"))
      (node (ref "U7") (pin "8") (pinfunction "GND_8") (pintype "power_in"))
      (node (ref "U8") (pin "1") (pinfunction "GND_1") (pintype "passive"))
      (node (ref "U8") (pin "10") (pinfunction "GND_10") (pintype "passive"))
      (node (ref "U8") (pin "3") (pinfunction "GND_3") (pintype "passive"))
      (node (ref "USBC1") (pin "A1") (pinfunction "GND_A1") (pintype "passive"))
      (node (ref "USBC1") (pin "A12") (pinfunction "GND_A12") (pintype "passive"))
      (node (ref "USBC1") (pin "B1") (pinfunction "GND_B1") (pintype "passive"))
      (node (ref "USBC1") (pin "B12") (pinfunction "GND_B12") (pintype "passive"))
      (node (ref "X1") (pin "2") (pinfunction "2_2") (pintype "passive"))
      (node (ref "X1") (pin "4") (pinfunction "4_4") (pintype "passive"))
    )
    (net (code "42") (name "Net-(LED1-K)") (class "Default")
      (node (ref "LED1") (pin "2") (pinfunction "K_2") (pintype "passive"))
      (node (ref "R6") (pin "1") (pinfunction "1_1") (pintype "passive"))
    )
    (net (code "43") (name "Net-(LED2-K)") (class "Default")
      (node (ref "LED2") (pin "2") (pinfunction "K_2") (pintype "passive"))
      (node (ref "R7") (pin "1") (pinfunction "1_1") (pintype "passive"))
    )
    (net (code "44") (name "Net-(Q2-Pad2)") (class "Default")
      (node (ref "Q2") (pin "2") (pinfunction "2_2") (pintype "passive"))
      (node (ref "U1") (pin "1") (pinfunction "1_1") (pintype "passive"))
    )
    (net (code "45") (name "Net-(Q3-D)") (class "Default")
      (node (ref "D1") (pin "1") (pinfunction "1_1") (pintype "passive"))
      (node (ref "Q3") (pin "3") (pinfunction "D_3") (pintype "passive"))
    )
    (net (code "46") (name "Net-(SMG1-A)") (class "Default")
      (node (ref "R15") (pin "2") (pinfunction "2_2") (pintype "passive"))
      (node (ref "SMG1") (pin "3") (pinfunction "A_3") (pintype "passive"))
    )
    (net (code "47") (name "Net-(SMG1-B)") (class "Default")
      (node (ref "R16") (pin "2") (pinfunction "2_2") (pintype "passive"))
      (node (ref "SMG1") (pin "9") (pinfunction "B_9") (pintype "passive"))
    )
    (net (code "48") (name "Net-(SMG1-C)") (class "Default")
      (node (ref "R17") (pin "2") (pinfunction "2_2") (pintype "passive"))
      (node (ref "SMG1") (pin "8") (pinfunction "C_8") (pintype "passive"))
    )
    (net (code "49") (name "Net-(SMG1-D)") (class "Default")
      (node (ref "R18") (pin "2") (pinfunction "2_2") (pintype "passive"))
      (node (ref "SMG1") (pin "6") (pinfunction "D_6") (pintype "passive"))
    )
    (net (code "50") (name "Net-(SMG1-E)") (class "Default")
      (node (ref "R19") (pin "2") (pinfunction "2_2") (pintype "passive"))
      (node (ref "SMG1") (pin "7") (pinfunction "E_7") (pintype "passive"))
    )
    (net (code "51") (name "Net-(SMG1-F)") (class "Default")
      (node (ref "R20") (pin "2") (pinfunction "2_2") (pintype "passive"))
      (node (ref "SMG1") (pin "4") (pinfunction "F_4") (pintype "passive"))
    )
    (net (code "52") (name "Net-(SMG1-G)") (class "Default")
      (node (ref "R21") (pin "2") (pinfunction "2_2") (pintype "passive"))
      (node (ref "SMG1") (pin "1") (pinfunction "G_1") (pintype "passive"))
    )
    (net (code "53") (name "Net-(SMG1-dp)") (class "Default")
      (node (ref "R22") (pin "2") (pinfunction "2_2") (pintype "passive"))
      (node (ref "SMG1") (pin "2") (pinfunction "dp_2") (pintype "passive"))
    )
    (net (code "54") (name "Net-(SMG2-A)") (class "Default")
      (node (ref "R23") (pin "2") (pinfunction "2_2") (pintype "passive"))
      (node (ref "SMG2") (pin "3") (pinfunction "A_3") (pintype "passive"))
    )
    (net (code "55") (name "Net-(SMG2-B)") (class "Default")
      (node (ref "R24") (pin "2") (pinfunction "2_2") (pintype "passive"))
      (node (ref "SMG2") (pin "9") (pinfunction "B_9") (pintype "passive"))
    )
    (net (code "56") (name "Net-(SMG2-C)") (class "Default")
      (node (ref "R25") (pin "2") (pinfunction "2_2") (pintype "passive"))
      (node (ref "SMG2") (pin "8") (pinfunction "C_8") (pintype "passive"))
    )
    (net (code "57") (name "Net-(SMG2-D)") (class "Default")
      (node (ref "R26") (pin "2") (pinfunction "2_2") (pintype "passive"))
      (node (ref "SMG2") (pin "6") (pinfunction "D_6") (pintype "passive"))
    )
    (net (code "58") (name "Net-(SMG2-E)") (class "Default")
      (node (ref "R27") (pin "2") (pinfunction "2_2") (pintype "passive"))
      (node (ref "SMG2") (pin "7") (pinfunction "E_7") (pintype "passive"))
    )
    (net (code "59") (name "Net-(SMG2-F)") (class "Default")
      (node (ref "R28") (pin "2") (pinfunction "2_2") (pintype "passive"))
      (node (ref "SMG2") (pin "4") (pinfunction "F_4") (pintype "passive"))
    )
    (net (code "60") (name "Net-(SMG2-G)") (class "Default")
      (node (ref "R29") (pin "2") (pinfunction "2_2") (pintype "passive"))
      (node (ref "SMG2") (pin "1") (pinfunction "G_1") (pintype "passive"))
    )
    (net (code "61") (name "Net-(SMG2-dp)") (class "Default")
      (node (ref "R30") (pin "2") (pinfunction "2_2") (pintype "passive"))
      (node (ref "SMG2") (pin "2") (pinfunction "dp_2") (pintype "passive"))
    )
    (net (code "62") (name "Net-(SMG3-A)") (class "Default")
      (node (ref "R31") (pin "2") (pinfunction "2_2") (pintype "passive"))
      (node (ref "SMG3") (pin "3") (pinfunction "A_3") (pintype "passive"))
    )
    (net (code "63") (name "Net-(SMG3-B)") (class "Default")
      (node (ref "R32") (pin "2") (pinfunction "2_2") (pintype "passive"))
      (node (ref "SMG3") (pin "9") (pinfunction "B_9") (pintype "passive"))
    )
    (net (code "64") (name "Net-(SMG3-C)") (class "Default")
      (node (ref "R33") (pin "2") (pinfunction "2_2") (pintype "passive"))
      (node (ref "SMG3") (pin "8") (pinfunction "C_8") (pintype "passive"))
    )
    (net (code "65") (name "Net-(SMG3-D)") (class "Default")
      (node (ref "R34") (pin "2") (pinfunction "2_2") (pintype "passive"))
      (node (ref "SMG3") (pin "6") (pinfunction "D_6") (pintype "passive"))
    )
    (net (code "66") (name "Net-(SMG3-E)") (class "Default")
      (node (ref "R35") (pin "2") (pinfunction "2_2") (pintype "passive"))
      (node (ref "SMG3") (pin "7") (pinfunction "E_7") (pintype "passive"))
    )
    (net (code "67") (name "Net-(SMG3-F)") (class "Default")
      (node (ref "R36") (pin "2") (pinfunction "2_2") (pintype "passive"))
      (node (ref "SMG3") (pin "4") (pinfunction "F_4") (pintype "passive"))
    )
    (net (code "68") (name "Net-(SMG3-G)") (class "Default")
      (node (ref "R37") (pin "2") (pinfunction "2_2") (pintype "passive"))
      (node (ref "SMG3") (pin "1") (pinfunction "G_1") (pintype "passive"))
    )
    (net (code "69") (name "Net-(SMG3-dp)") (class "Default")
      (node (ref "R38") (pin "2") (pinfunction "2_2") (pintype "passive"))
      (node (ref "SMG3") (pin "2") (pinfunction "dp_2") (pintype "passive"))
    )
    (net (code "70") (name "Net-(U2-CHRG)") (class "Default")
      (node (ref "R6") (pin "2") (pinfunction "2_2") (pintype "passive"))
      (node (ref "U2") (pin "7") (pinfunction "CHRG_7") (pintype "passive"))
    )
    (net (code "71") (name "Net-(U2-PROG)") (class "Default")
      (node (ref "R5") (pin "2") (pinfunction "2_2") (pintype "passive"))
      (node (ref "U2") (pin "2") (pinfunction "PROG_2") (pintype "passive"))
    )
    (net (code "72") (name "Net-(U2-STDBY)") (class "Default")
      (node (ref "R7") (pin "2") (pinfunction "2_2") (pintype "passive"))
      (node (ref "U2") (pin "6") (pinfunction "STDBY_6") (pintype "passive"))
    )
    (net (code "73") (name "Net-(U6-QH1)") (class "Default")
      (node (ref "U6") (pin "9") (pinfunction "QH1_9") (pintype "output"))
      (node (ref "U7") (pin "14") (pinfunction "SER_14") (pintype "input"))
    )
    (net (code "74") (name "Net-(U8-ANT)") (class "Default")
      (node (ref "L1") (pin "2") (pinfunction "2_2") (pintype "passive"))
      (node (ref "U8") (pin "2") (pinfunction "ANT_2") (pintype "passive"))
    )
    (net (code "75") (name "Net-(U8-VCC_RF)") (class "Default")
      (node (ref "L1") (pin "1") (pinfunction "1_1") (pintype "passive"))
      (node (ref "U8") (pin "5") (pinfunction "VCC_RF_5") (pintype "passive"))
    )
    (net (code "76") (name "VBUS") (class "Default")
      (node (ref "D1") (pin "2") (pinfunction "2_2") (pintype "passive"))
      (node (ref "E2") (pin "1") (pinfunction "A_1") (pintype "passive"))
      (node (ref "LED1") (pin "1") (pinfunction "A_1") (pintype "passive"))
      (node (ref "LED2") (pin "1") (pinfunction "A_1") (pintype "passive"))
      (node (ref "Q3") (pin "1") (pinfunction "G_1") (pintype "passive"))
      (node (ref "R8") (pin "2") (pinfunction "2_2") (pintype "passive"))
      (node (ref "U2") (pin "4") (pinfunction "VCC_4") (pintype "passive"))
      (node (ref "U2") (pin "8") (pinfunction "CE_8") (pintype "passive"))
      (node (ref "USBC1") (pin "A4") (pinfunction "VBUS_A4") (pintype "passive"))
      (node (ref "USBC1") (pin "A9") (pinfunction "VBUS_A9") (pintype "passive"))
      (node (ref "USBC1") (pin "B4") (pinfunction "VBUS_B4") (pintype "passive"))
      (node (ref "USBC1") (pin "B9") (pinfunction "VBUS_B9") (pintype "passive"))
    )
    (net (code "77") (name "VCC") (class "Default")
      (node (ref "U6") (pin "16") (pinfunction "VCC_16") (pintype "power_in"))
      (node (ref "U7") (pin "16") (pinfunction "VCC_16") (pintype "power_in"))
    )
    (net (code "78") (name "VM") (class "Default")
      (node (ref "D1") (pin "3") (pinfunction "3_3") (pintype "passive"))
      (node (ref "E1") (pin "1") (pinfunction "A_1") (pintype "passive"))
      (node (ref "U3") (pin "1") (pinfunction "VIN_1") (pintype "passive"))
      (node (ref "U3") (pin "3") (pinfunction "EN_3") (pintype "passive"))
      (node (ref "U4") (pin "1") (pinfunction "VIN_1") (pintype "passive"))
      (node (ref "U4") (pin "3") (pinfunction "EN_3") (pintype "passive"))
      (node (ref "U5") (pin "1") (pinfunction "VIN_1") (pintype "passive"))
      (node (ref "U5") (pin "3") (pinfunction "EN_3") (pintype "passive"))
    )
    (net (code "79") (name "unconnected-(K1-Pad1)") (class "Default")
      (node (ref "K1") (pin "1") (pintype "passive+no_connect"))
    )
    (net (code "80") (name "unconnected-(K1-Pad2)") (class "Default")
      (node (ref "K1") (pin "2") (pintype "passive+no_connect"))
    )
    (net (code "81") (name "unconnected-(K2-Pad1)") (class "Default")
      (node (ref "K2") (pin "1") (pintype "passive+no_connect"))
    )
    (net (code "82") (name "unconnected-(K2-Pad2)") (class "Default")
      (node (ref "K2") (pin "2") (pintype "passive+no_connect"))
    )
    (net (code "83") (name "unconnected-(K3-Pad1)") (class "Default")
      (node (ref "K3") (pin "1") (pintype "passive+no_connect"))
    )
    (net (code "84") (name "unconnected-(K3-Pad2)") (class "Default")
      (node (ref "K3") (pin "2") (pintype "passive+no_connect"))
    )
    (net (code "85") (name "unconnected-(K4-Pad1)") (class "Default")
      (node (ref "K4") (pin "1") (pintype "passive+no_connect"))
    )
    (net (code "86") (name "unconnected-(K4-Pad2)") (class "Default")
      (node (ref "K4") (pin "2") (pintype "passive+no_connect"))
    )
    (net (code "87") (name "unconnected-(U1-Pad19)") (class "Default")
      (node (ref "U1") (pin "19") (pinfunction "19_19") (pintype "passive+no_connect"))
    )
    (net (code "88") (name "unconnected-(U1-Pad20)") (class "Default")
      (node (ref "U1") (pin "20") (pinfunction "20_20") (pintype "passive+no_connect"))
    )
    (net (code "89") (name "unconnected-(U1-Pad21)") (class "Default")
      (node (ref "U1") (pin "21") (pinfunction "21_21") (pintype "passive+no_connect"))
    )
    (net (code "90") (name "unconnected-(U1-Pad22)") (class "Default")
      (node (ref "U1") (pin "22") (pinfunction "22_22") (pintype "passive+no_connect"))
    )
    (net (code "91") (name "unconnected-(U1-Pad23)") (class "Default")
      (node (ref "U1") (pin "23") (pinfunction "23_23") (pintype "passive+no_connect"))
    )
    (net (code "92") (name "unconnected-(U1-Pad24)") (class "Default")
      (node (ref "U1") (pin "24") (pinfunction "24_24") (pintype "passive+no_connect"))
    )
    (net (code "93") (name "unconnected-(U3-BP-Pad4)") (class "Default")
      (node (ref "U3") (pin "4") (pinfunction "BP_4") (pintype "passive+no_connect"))
    )
    (net (code "94") (name "unconnected-(U4-BP-Pad4)") (class "Default")
      (node (ref "U4") (pin "4") (pinfunction "BP_4") (pintype "passive+no_connect"))
    )
    (net (code "95") (name "unconnected-(U5-BP-Pad4)") (class "Default")
      (node (ref "U5") (pin "4") (pinfunction "BP_4") (pintype "passive+no_connect"))
    )
    (net (code "96") (name "unconnected-(U7-QG-Pad6)") (class "Default")
      (node (ref "U7") (pin "6") (pinfunction "QG_6") (pintype "output+no_connect"))
    )
    (net (code "97") (name "unconnected-(U7-QH-Pad7)") (class "Default")
      (node (ref "U7") (pin "7") (pinfunction "QH_7") (pintype "tri_state+no_connect"))
    )
    (net (code "98") (name "unconnected-(U7-QH1-Pad9)") (class "Default")
      (node (ref "U7") (pin "9") (pinfunction "QH1_9") (pintype "output+no_connect"))
    )
    (net (code "99") (name "unconnected-(U8-NC-Pad4)") (class "Default")
      (node (ref "U8") (pin "4") (pinfunction "NC_4") (pintype "passive+no_connect"))
    )
    (net (code "100") (name "unconnected-(U8-NC-Pad16)") (class "Default")
      (node (ref "U8") (pin "16") (pinfunction "NC_16") (pintype "passive+no_connect"))
    )
    (net (code "101") (name "unconnected-(U8-NRST-Pad18)") (class "Default")
      (node (ref "U8") (pin "18") (pinfunction "NRST_18") (pintype "passive+no_connect"))
    )
    (net (code "102") (name "unconnected-(U8-PPS-Pad13)") (class "Default")
      (node (ref "U8") (pin "13") (pinfunction "PPS_13") (pintype "passive+no_connect"))
    )
    (net (code "103") (name "unconnected-(U8-SCL-Pad8)") (class "Default")
      (node (ref "U8") (pin "8") (pinfunction "SCL_8") (pintype "passive+no_connect"))
    )
    (net (code "104") (name "unconnected-(U8-SDA-Pad7)") (class "Default")
      (node (ref "U8") (pin "7") (pinfunction "SDA_7") (pintype "passive+no_connect"))
    )
    (net (code "105") (name "unconnected-(U8-TCK-Pad9)") (class "Default")
      (node (ref "U8") (pin "9") (pinfunction "TCK_9") (pintype "passive+no_connect"))
    )
    (net (code "106") (name "unconnected-(U8-TMS-Pad6)") (class "Default")
      (node (ref "U8") (pin "6") (pinfunction "TMS_6") (pintype "passive+no_connect"))
    )
    (net (code "107") (name "unconnected-(USBC1-CC1-PadA5)") (class "Default")
      (node (ref "USBC1") (pin "A5") (pinfunction "CC1_A5") (pintype "passive+no_connect"))
    )
    (net (code "108") (name "unconnected-(USBC1-CC2-PadB5)") (class "Default")
      (node (ref "USBC1") (pin "B5") (pinfunction "CC2_B5") (pintype "passive+no_connect"))
    )
    (net (code "109") (name "unconnected-(USBC1-Pad0)") (class "Default")
      (node (ref "USBC1") (pin "0") (pinfunction "0_0") (pintype "passive+no_connect"))
    )
    (net (code "110") (name "unconnected-(USBC1-Pad0)_1") (class "Default")
      (node (ref "USBC1") (pin "0") (pinfunction "0_0") (pintype "passive+no_connect"))
    )
    (net (code "111") (name "unconnected-(USBC1-Pad0)_2") (class "Default")
      (node (ref "USBC1") (pin "0") (pinfunction "0_0") (pintype "passive+no_connect"))
    )
    (net (code "112") (name "unconnected-(USBC1-Pad0)_3") (class "Default")
      (node (ref "USBC1") (pin "0") (pinfunction "0_0") (pintype "passive+no_connect"))
    )
    (net (code "113") (name "unconnected-(USBC1-SBU1-PadA8)") (class "Default")
      (node (ref "USBC1") (pin "A8") (pinfunction "SBU1_A8") (pintype "passive+no_connect"))
    )
    (net (code "114") (name "unconnected-(USBC1-SBU2-PadB8)") (class "Default")
      (node (ref "USBC1") (pin "B8") (pinfunction "SBU2_B8") (pintype "passive+no_connect"))
    )
  )
)
